# breakout_STM32F030F4P6_2.net
KiCad netlist of a schematic drawn in EAGLE
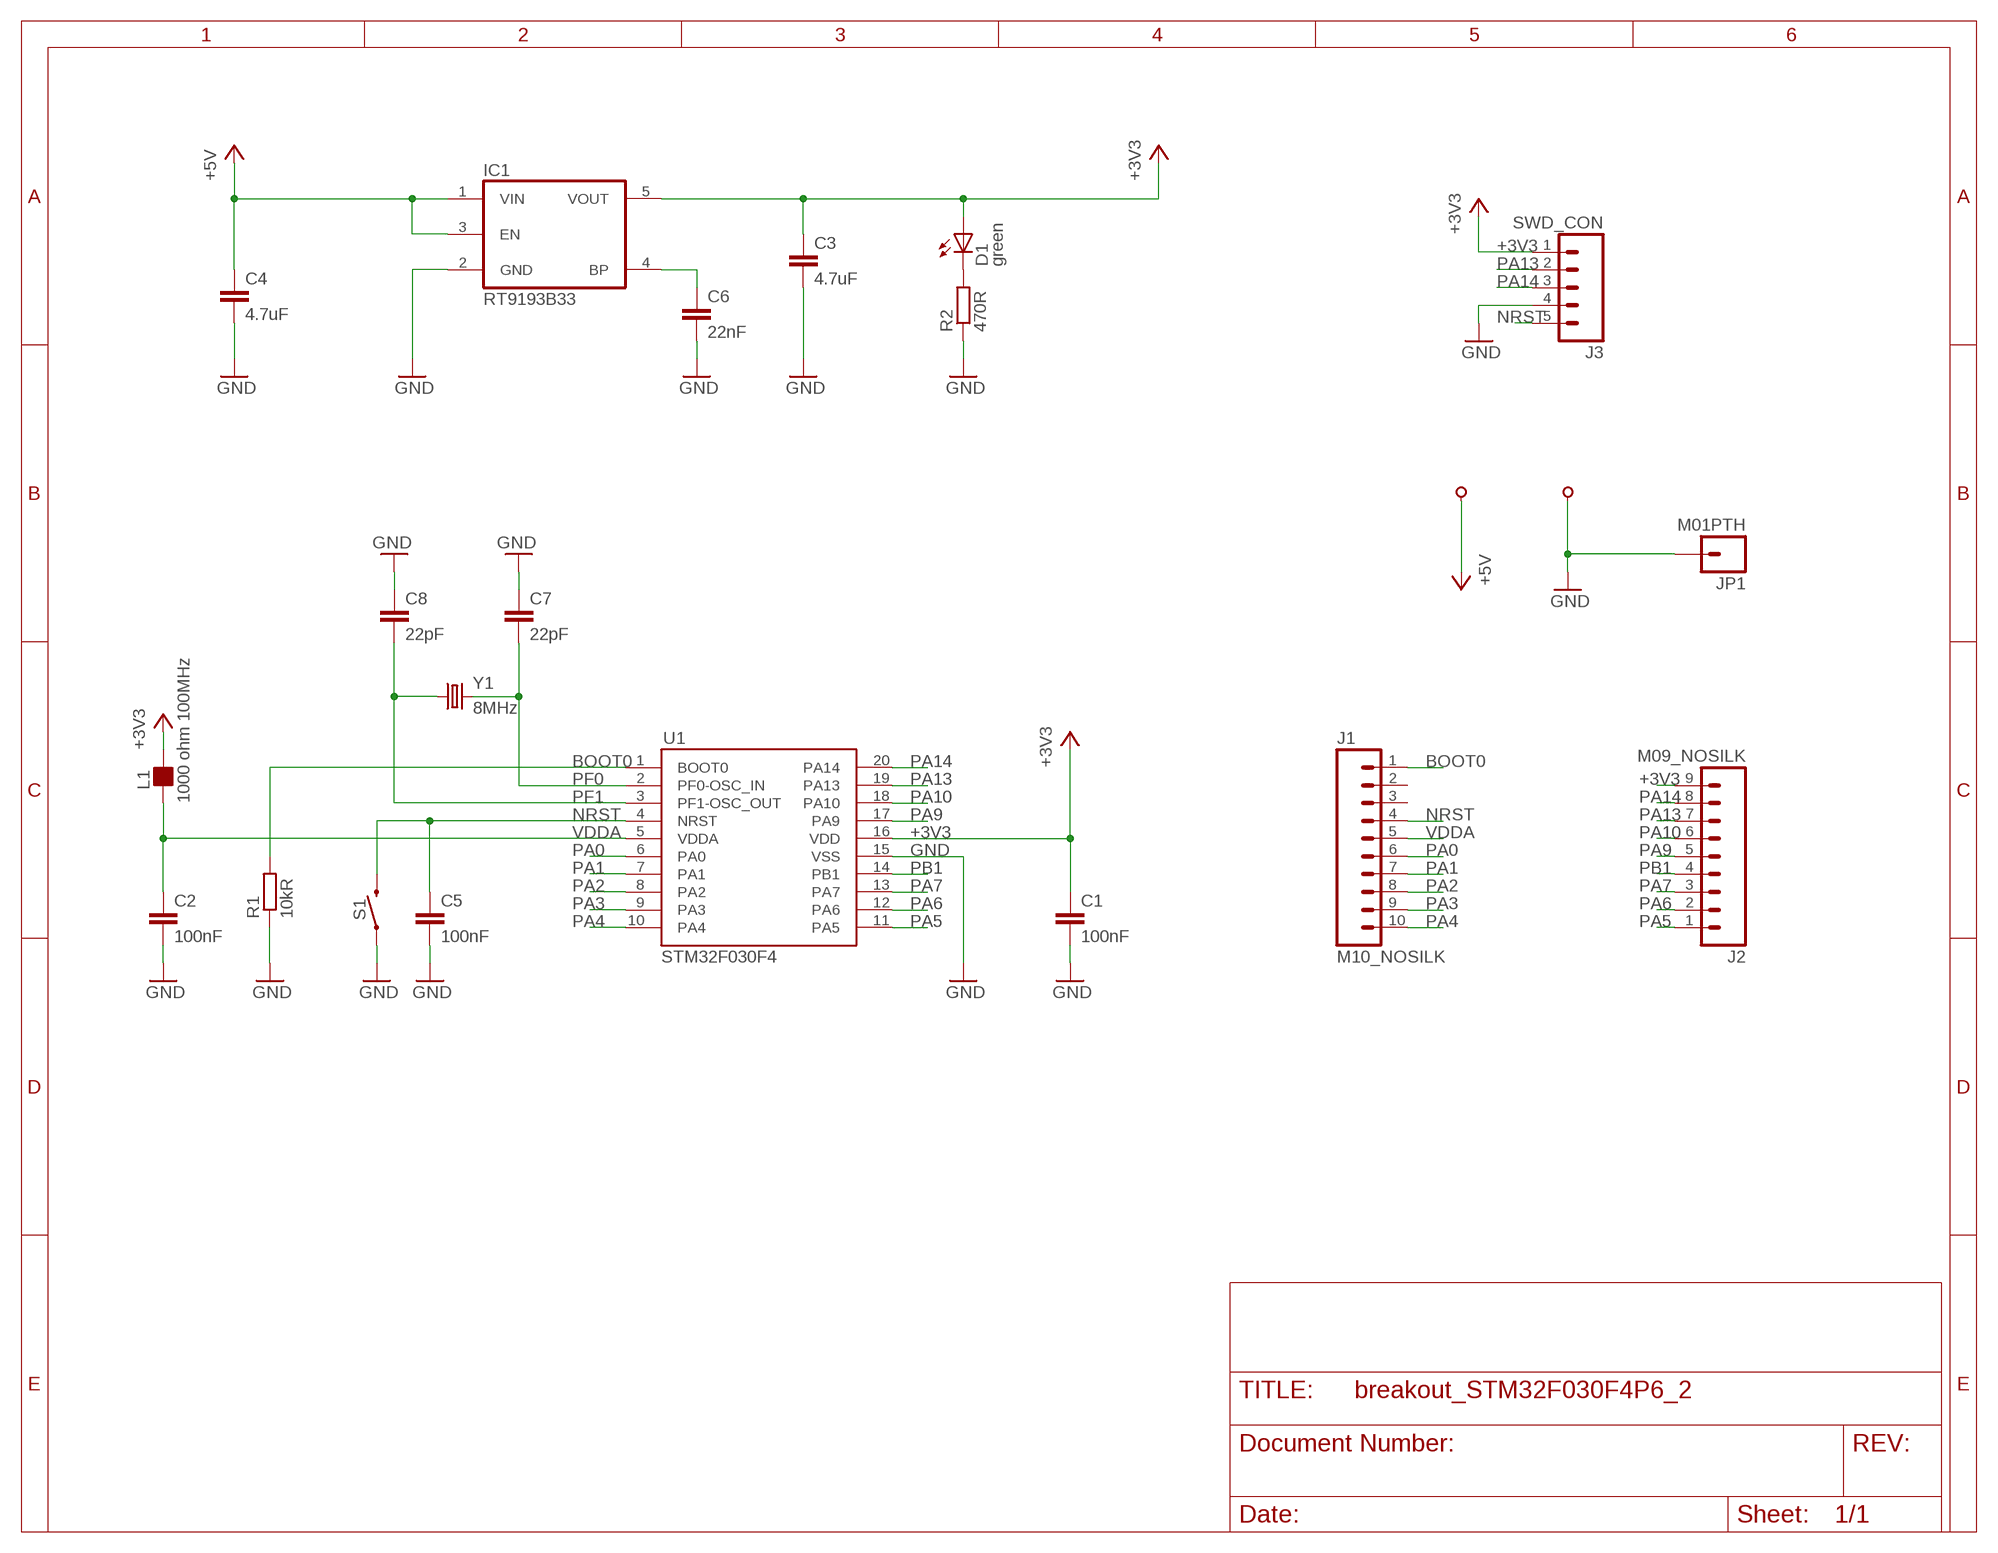
[diagram p0: schematic, sheet 1]

(export (version "E")
  (design (tool "Eeschema 10.0.6"))
  (components
    (comp (ref "5V")
      (value "M01_1SQ")
      (footprint "eagle-import:M01_1SQ")
      (libsource (lib "eagle-import") (part "M01_1SQ"))
    )
    (comp (ref "C1")
      (value "100nF")
      (footprint "eagle-import:C0805")
      (libsource (lib "eagle-import") (part "C-EUC0805"))
    )
    (comp (ref "C2")
      (value "100nF")
      (footprint "eagle-import:C0805")
      (libsource (lib "eagle-import") (part "C-EUC0805"))
    )
    (comp (ref "C3")
      (value "4.7uF")
      (footprint "eagle-import:C3216")
      (libsource (lib "eagle-import") (part "resistor_C-EUC3216"))
    )
    (comp (ref "C4")
      (value "4.7uF")
      (footprint "eagle-import:C3216")
      (libsource (lib "eagle-import") (part "resistor_C-EUC3216"))
    )
    (comp (ref "C5")
      (value "100nF")
      (footprint "eagle-import:C0805")
      (libsource (lib "eagle-import") (part "C-EUC0805"))
    )
    (comp (ref "C6")
      (value "22nF")
      (footprint "eagle-import:C0805")
      (libsource (lib "eagle-import") (part "resistor_C-EUC0805"))
    )
    (comp (ref "C7")
      (value "22pF")
      (footprint "eagle-import:C0805")
      (libsource (lib "eagle-import") (part "resistor_C-EUC0805"))
    )
    (comp (ref "C8")
      (value "22pF")
      (footprint "eagle-import:C0805")
      (libsource (lib "eagle-import") (part "resistor_C-EUC0805"))
    )
    (comp (ref "D1")
      (value "green")
      (footprint "eagle-import:SML0805")
      (libsource (lib "eagle-import") (part "LEDSML0805"))
    )
    (comp (ref "GND")
      (value "M01_NOSILK")
      (footprint "eagle-import:M01_NOSILK")
      (libsource (lib "eagle-import") (part "M01_NOSILK"))
    )
    (comp (ref "IC1")
      (value "RT9193B33")
      (footprint "eagle-import:TSOT23-5")
      (libsource (lib "eagle-import") (part "RT919333B"))
    )
    (comp (ref "J1")
      (value "M10_NOSILK")
      (footprint "eagle-import:M10_NOSILK")
      (libsource (lib "eagle-import") (part "M10_NOSILK"))
    )
    (comp (ref "J2")
      (value "M09_NOSILK")
      (footprint "eagle-import:M09_NOSILK")
      (libsource (lib "eagle-import") (part "M09_NOSILK"))
    )
    (comp (ref "J3")
      (value "SWD_CON")
      (footprint "eagle-import:M05_NOSILK_1SQ")
      (libsource (lib "eagle-import") (part "M05_NOSILK_1SQ"))
    )
    (comp (ref "JP1")
      (value "M01PTH")
      (footprint "eagle-import:1X01")
      (libsource (lib "eagle-import") (part "M01PTH"))
    )
    (comp (ref "L1")
      (value "1000 ohm 100MHz")
      (footprint "eagle-import:L0805")
      (libsource (lib "eagle-import") (part "FB_0805"))
    )
    (comp (ref "R1")
      (value "10kR")
      (footprint "eagle-import:R0805")
      (libsource (lib "eagle-import") (part "R-EU_R0805"))
    )
    (comp (ref "R2")
      (value "470R")
      (footprint "eagle-import:R0805")
      (libsource (lib "eagle-import") (part "R-EU_R0805"))
    )
    (comp (ref "S1")
      (value "MOMENTARY-SWITCH-SPST-SMD-5.2MM")
      (footprint "eagle-import:TACTILE_SWITCH_SMD_5.2MM")
      (libsource (lib "eagle-import") (part "MOMENTARY-SWITCH-SPST-SMD-5.2MM"))
    )
    (comp (ref "U1")
      (value "STM32F030F4")
      (footprint "eagle-import:TSSOP-20")
      (libsource (lib "eagle-import") (part "STM32F030F4"))
    )
    (comp (ref "Y1")
      (value "8MHz")
      (footprint "eagle-import:CRYSTAL-SMD-5X3")
      (libsource (lib "eagle-import") (part "CRYSTAL5X3"))
    )
  )
  (nets
    (net (code "1") (name "+3V3") (class "Default")
      (node (ref "C1") (pin "1") (pinfunction "1_1") (pintype "passive"))
      (node (ref "C3") (pin "1") (pinfunction "1_1") (pintype "passive"))
      (node (ref "D1") (pin "A") (pinfunction "A_A") (pintype "passive"))
      (node (ref "IC1") (pin "5") (pinfunction "VOUT_5") (pintype "output"))
      (node (ref "J2") (pin "9") (pinfunction "9_9") (pintype "passive"))
      (node (ref "J3") (pin "1") (pinfunction "1_1") (pintype "passive"))
      (node (ref "L1") (pin "2") (pinfunction "2_2") (pintype "passive"))
      (node (ref "U1") (pin "16") (pinfunction "VDD_16") (pintype "bidirectional"))
    )
    (net (code "2") (name "+5V") (class "Default")
      (node (ref "5V") (pin "1") (pinfunction "1_1") (pintype "bidirectional"))
      (node (ref "C4") (pin "1") (pinfunction "1_1") (pintype "passive"))
      (node (ref "IC1") (pin "1") (pinfunction "VIN_1") (pintype "power_in"))
      (node (ref "IC1") (pin "3") (pinfunction "EN_3") (pintype "passive"))
    )
    (net (code "3") (name "/BOOT0") (class "Default")
      (node (ref "J1") (pin "1") (pinfunction "1_1") (pintype "passive"))
      (node (ref "R1") (pin "2") (pinfunction "2_2") (pintype "passive"))
      (node (ref "U1") (pin "1") (pinfunction "BOOT0_1") (pintype "bidirectional"))
    )
    (net (code "4") (name "/NRST") (class "Default")
      (node (ref "C5") (pin "1") (pinfunction "1_1") (pintype "passive"))
      (node (ref "J1") (pin "4") (pinfunction "4_4") (pintype "passive"))
      (node (ref "J3") (pin "5") (pinfunction "5_5") (pintype "passive"))
      (node (ref "S1") (pin "3") (pinfunction "2_3") (pintype "passive"))
      (node (ref "U1") (pin "4") (pinfunction "NRST_4") (pintype "bidirectional"))
    )
    (net (code "5") (name "/PA0") (class "Default")
      (node (ref "J1") (pin "6") (pinfunction "6_6") (pintype "passive"))
      (node (ref "U1") (pin "6") (pinfunction "PA0_6") (pintype "bidirectional"))
    )
    (net (code "6") (name "/PA1") (class "Default")
      (node (ref "J1") (pin "7") (pinfunction "7_7") (pintype "passive"))
      (node (ref "U1") (pin "7") (pinfunction "PA1_7") (pintype "bidirectional"))
    )
    (net (code "7") (name "/PA2") (class "Default")
      (node (ref "J1") (pin "8") (pinfunction "8_8") (pintype "passive"))
      (node (ref "U1") (pin "8") (pinfunction "PA2_8") (pintype "bidirectional"))
    )
    (net (code "8") (name "/PA3") (class "Default")
      (node (ref "J1") (pin "9") (pinfunction "9_9") (pintype "passive"))
      (node (ref "U1") (pin "9") (pinfunction "PA3_9") (pintype "bidirectional"))
    )
    (net (code "9") (name "/PA4") (class "Default")
      (node (ref "J1") (pin "10") (pinfunction "10_10") (pintype "passive"))
      (node (ref "U1") (pin "10") (pinfunction "PA4_10") (pintype "bidirectional"))
    )
    (net (code "10") (name "/PA5") (class "Default")
      (node (ref "J2") (pin "1") (pinfunction "1_1") (pintype "passive"))
      (node (ref "U1") (pin "11") (pinfunction "PA5_11") (pintype "bidirectional"))
    )
    (net (code "11") (name "/PA6") (class "Default")
      (node (ref "J2") (pin "2") (pinfunction "2_2") (pintype "passive"))
      (node (ref "U1") (pin "12") (pinfunction "PA6_12") (pintype "bidirectional"))
    )
    (net (code "12") (name "/PA7") (class "Default")
      (node (ref "J2") (pin "3") (pinfunction "3_3") (pintype "passive"))
      (node (ref "U1") (pin "13") (pinfunction "PA7_13") (pintype "bidirectional"))
    )
    (net (code "13") (name "/PA9") (class "Default")
      (node (ref "J2") (pin "5") (pinfunction "5_5") (pintype "passive"))
      (node (ref "U1") (pin "17") (pinfunction "PA9_17") (pintype "bidirectional"))
    )
    (net (code "14") (name "/PA10") (class "Default")
      (node (ref "J2") (pin "6") (pinfunction "6_6") (pintype "passive"))
      (node (ref "U1") (pin "18") (pinfunction "PA10_18") (pintype "bidirectional"))
    )
    (net (code "15") (name "/PA13") (class "Default")
      (node (ref "J2") (pin "7") (pinfunction "7_7") (pintype "passive"))
      (node (ref "J3") (pin "2") (pinfunction "2_2") (pintype "passive"))
      (node (ref "U1") (pin "19") (pinfunction "PA13_19") (pintype "bidirectional"))
    )
    (net (code "16") (name "/PA14") (class "Default")
      (node (ref "J2") (pin "8") (pinfunction "8_8") (pintype "passive"))
      (node (ref "J3") (pin "3") (pinfunction "3_3") (pintype "passive"))
      (node (ref "U1") (pin "20") (pinfunction "PA14_20") (pintype "bidirectional"))
    )
    (net (code "17") (name "/PB1") (class "Default")
      (node (ref "J2") (pin "4") (pinfunction "4_4") (pintype "passive"))
      (node (ref "U1") (pin "14") (pinfunction "PB1_14") (pintype "bidirectional"))
    )
    (net (code "18") (name "/PF0") (class "Default")
      (node (ref "C7") (pin "2") (pinfunction "2_2") (pintype "passive"))
      (node (ref "U1") (pin "2") (pinfunction "PF0-OSC_IN_2") (pintype "bidirectional"))
      (node (ref "Y1") (pin "3") (pinfunction "2_3") (pintype "passive"))
    )
    (net (code "19") (name "/PF1") (class "Default")
      (node (ref "C8") (pin "2") (pinfunction "2_2") (pintype "passive"))
      (node (ref "U1") (pin "3") (pinfunction "PF1-OSC_OUT_3") (pintype "bidirectional"))
      (node (ref "Y1") (pin "1") (pinfunction "1_1") (pintype "passive"))
    )
    (net (code "20") (name "/VDDA") (class "Default")
      (node (ref "C2") (pin "1") (pinfunction "1_1") (pintype "passive"))
      (node (ref "J1") (pin "5") (pinfunction "5_5") (pintype "passive"))
      (node (ref "L1") (pin "1") (pinfunction "1_1") (pintype "passive"))
      (node (ref "U1") (pin "5") (pinfunction "VDDA_5") (pintype "bidirectional"))
    )
    (net (code "21") (name "GND") (class "Default")
      (node (ref "C1") (pin "2") (pinfunction "2_2") (pintype "passive"))
      (node (ref "C2") (pin "2") (pinfunction "2_2") (pintype "passive"))
      (node (ref "C3") (pin "2") (pinfunction "2_2") (pintype "passive"))
      (node (ref "C4") (pin "2") (pinfunction "2_2") (pintype "passive"))
      (node (ref "C5") (pin "2") (pinfunction "2_2") (pintype "passive"))
      (node (ref "C6") (pin "2") (pinfunction "2_2") (pintype "passive"))
      (node (ref "C7") (pin "1") (pinfunction "1_1") (pintype "passive"))
      (node (ref "C8") (pin "1") (pinfunction "1_1") (pintype "passive"))
      (node (ref "GND") (pin "1") (pinfunction "1_1") (pintype "bidirectional"))
      (node (ref "IC1") (pin "2") (pinfunction "GND_2") (pintype "power_in"))
      (node (ref "J3") (pin "4") (pinfunction "4_4") (pintype "passive"))
      (node (ref "JP1") (pin "1") (pinfunction "1_1") (pintype "passive"))
      (node (ref "R1") (pin "1") (pinfunction "1_1") (pintype "passive"))
      (node (ref "R2") (pin "1") (pinfunction "1_1") (pintype "passive"))
      (node (ref "S1") (pin "1") (pinfunction "1_1") (pintype "passive"))
      (node (ref "U1") (pin "15") (pinfunction "VSS_15") (pintype "bidirectional"))
    )
    (net (code "22") (name "Net-(D1-PadC)") (class "Default")
      (node (ref "D1") (pin "C") (pinfunction "C_C") (pintype "passive"))
      (node (ref "R2") (pin "2") (pinfunction "2_2") (pintype "passive"))
    )
    (net (code "23") (name "Net-(IC1-BP)") (class "Default")
      (node (ref "C6") (pin "1") (pinfunction "1_1") (pintype "passive"))
      (node (ref "IC1") (pin "4") (pinfunction "BP_4") (pintype "passive"))
    )
    (net (code "24") (name "unconnected-(J1-Pad2)") (class "Default")
      (node (ref "J1") (pin "2") (pinfunction "2_2") (pintype "passive"))
    )
    (net (code "25") (name "unconnected-(J1-Pad3)") (class "Default")
      (node (ref "J1") (pin "3") (pinfunction "3_3") (pintype "passive"))
    )
  )
)
